# IR_array.net
KiCad netlist of a schematic drawn in Altium Designer
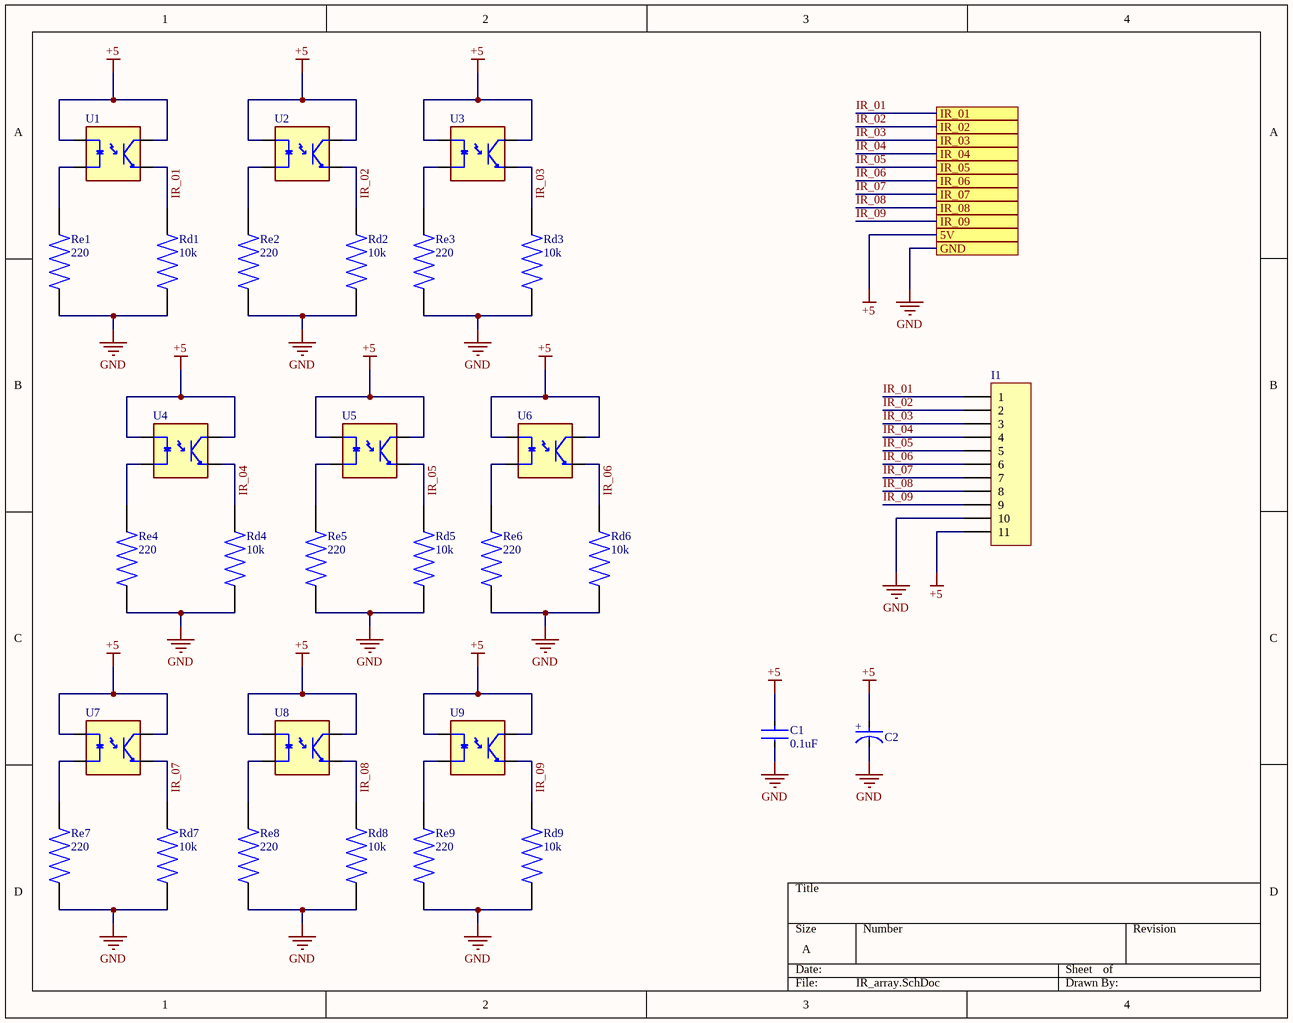
[diagram p0: IR_array.SchDoc]

(export (version "E")
  (design (tool "Eeschema 10.0.6"))
  (components
    (comp (ref "C1")
      (value "0.1uF")
      (footprint "FP-RDE0P1-MFG")
      (description "Ceramic Capacitor 100nF ±10% 25V X7R Radial")
      (fields (field (name "TOLERANCE") "10%"))
      (libsource (lib "0.1uF 25V cap cer TH") (part "CMP-06035-046728-1"))
    )
    (comp (ref "C2")
      (value "ECEA1CKA101I")
      (footprint "FP-RAD-TH-D_6_3_0_5-L_7_1-MFG")
      (description "Aluminum Electrolytic Capacitors (Radial Lead Type) 100uF ±20% 16V")
      (fields (field (name "VOLTAGE") "16V") (field (name "TOLERANCE") "20%"))
      (libsource (lib "100uF 16V cap TH") (part "CMP-05427-001316-1"))
    )
    (comp (ref "I1")
      (value "MHP1x11")
      (footprint "MHPC1x11:MHPC1x11")
      (libsource (lib "MHPC1x11") (part "MHP1x11"))
    )
    (comp (ref "Rd1")
      (value "10k")
      (footprint "RESAD1100W55L680D260")
      (description "1.07 kOhms Â±1% 0.25W, 1/4W Through Hole Resistor Axial - Metal Film")
      (fields (field (name "MF") "Yageo") (field (name "MP") "MFR-25FBF52-1K"))
      (libsource (lib "REG_th") (part "MFR-25FBF52-1K"))
    )
    (comp (ref "Rd2")
      (value "10k")
      (footprint "RESAD1100W55L680D260")
      (description "1.07 kOhms Â±1% 0.25W, 1/4W Through Hole Resistor Axial - Metal Film")
      (fields (field (name "MF") "Yageo") (field (name "MP") "MFR-25FBF52-1K"))
      (libsource (lib "REG_th") (part "MFR-25FBF52-1K"))
    )
    (comp (ref "Rd3")
      (value "10k")
      (footprint "RESAD1100W55L680D260")
      (description "1.07 kOhms Â±1% 0.25W, 1/4W Through Hole Resistor Axial - Metal Film")
      (fields (field (name "MF") "Yageo") (field (name "MP") "MFR-25FBF52-1K"))
      (libsource (lib "REG_th") (part "MFR-25FBF52-1K"))
    )
    (comp (ref "Rd4")
      (value "10k")
      (footprint "RESAD1100W55L680D260")
      (description "1.07 kOhms Â±1% 0.25W, 1/4W Through Hole Resistor Axial - Metal Film")
      (fields (field (name "MF") "Yageo") (field (name "MP") "MFR-25FBF52-1K"))
      (libsource (lib "REG_th") (part "MFR-25FBF52-1K"))
    )
    (comp (ref "Rd5")
      (value "10k")
      (footprint "RESAD1100W55L680D260")
      (description "1.07 kOhms Â±1% 0.25W, 1/4W Through Hole Resistor Axial - Metal Film")
      (fields (field (name "MF") "Yageo") (field (name "MP") "MFR-25FBF52-1K"))
      (libsource (lib "REG_th") (part "MFR-25FBF52-1K"))
    )
    (comp (ref "Rd6")
      (value "10k")
      (footprint "RESAD1100W55L680D260")
      (description "1.07 kOhms Â±1% 0.25W, 1/4W Through Hole Resistor Axial - Metal Film")
      (fields (field (name "MF") "Yageo") (field (name "MP") "MFR-25FBF52-1K"))
      (libsource (lib "REG_th") (part "MFR-25FBF52-1K"))
    )
    (comp (ref "Rd7")
      (value "10k")
      (footprint "RESAD1100W55L680D260")
      (description "1.07 kOhms Â±1% 0.25W, 1/4W Through Hole Resistor Axial - Metal Film")
      (fields (field (name "MF") "Yageo") (field (name "MP") "MFR-25FBF52-1K"))
      (libsource (lib "REG_th") (part "MFR-25FBF52-1K"))
    )
    (comp (ref "Rd8")
      (value "10k")
      (footprint "RESAD1100W55L680D260")
      (description "1.07 kOhms Â±1% 0.25W, 1/4W Through Hole Resistor Axial - Metal Film")
      (fields (field (name "MF") "Yageo") (field (name "MP") "MFR-25FBF52-1K"))
      (libsource (lib "REG_th") (part "MFR-25FBF52-1K"))
    )
    (comp (ref "Rd9")
      (value "10k")
      (footprint "RESAD1100W55L680D260")
      (description "1.07 kOhms Â±1% 0.25W, 1/4W Through Hole Resistor Axial - Metal Film")
      (fields (field (name "MF") "Yageo") (field (name "MP") "MFR-25FBF52-1K"))
      (libsource (lib "REG_th") (part "MFR-25FBF52-1K"))
    )
    (comp (ref "Re1")
      (value "220")
      (footprint "RESAD1100W55L680D260")
      (description "1.07 kOhms Â±1% 0.25W, 1/4W Through Hole Resistor Axial - Metal Film")
      (fields (field (name "MF") "Yageo") (field (name "MP") "MFR-25FBF52-1K"))
      (libsource (lib "REG_th") (part "MFR-25FBF52-1K"))
    )
    (comp (ref "Re2")
      (value "220")
      (footprint "RESAD1100W55L680D260")
      (description "1.07 kOhms Â±1% 0.25W, 1/4W Through Hole Resistor Axial - Metal Film")
      (fields (field (name "MF") "Yageo") (field (name "MP") "MFR-25FBF52-1K"))
      (libsource (lib "REG_th") (part "MFR-25FBF52-1K"))
    )
    (comp (ref "Re3")
      (value "220")
      (footprint "RESAD1100W55L680D260")
      (description "1.07 kOhms Â±1% 0.25W, 1/4W Through Hole Resistor Axial - Metal Film")
      (fields (field (name "MF") "Yageo") (field (name "MP") "MFR-25FBF52-1K"))
      (libsource (lib "REG_th") (part "MFR-25FBF52-1K"))
    )
    (comp (ref "Re4")
      (value "220")
      (footprint "RESAD1100W55L680D260")
      (description "1.07 kOhms Â±1% 0.25W, 1/4W Through Hole Resistor Axial - Metal Film")
      (fields (field (name "MF") "Yageo") (field (name "MP") "MFR-25FBF52-1K"))
      (libsource (lib "REG_th") (part "MFR-25FBF52-1K"))
    )
    (comp (ref "Re5")
      (value "220")
      (footprint "RESAD1100W55L680D260")
      (description "1.07 kOhms Â±1% 0.25W, 1/4W Through Hole Resistor Axial - Metal Film")
      (fields (field (name "MF") "Yageo") (field (name "MP") "MFR-25FBF52-1K"))
      (libsource (lib "REG_th") (part "MFR-25FBF52-1K"))
    )
    (comp (ref "Re6")
      (value "220")
      (footprint "RESAD1100W55L680D260")
      (description "1.07 kOhms Â±1% 0.25W, 1/4W Through Hole Resistor Axial - Metal Film")
      (fields (field (name "MF") "Yageo") (field (name "MP") "MFR-25FBF52-1K"))
      (libsource (lib "REG_th") (part "MFR-25FBF52-1K"))
    )
    (comp (ref "Re7")
      (value "220")
      (footprint "RESAD1100W55L680D260")
      (description "1.07 kOhms Â±1% 0.25W, 1/4W Through Hole Resistor Axial - Metal Film")
      (fields (field (name "MF") "Yageo") (field (name "MP") "MFR-25FBF52-1K"))
      (libsource (lib "REG_th") (part "MFR-25FBF52-1K"))
    )
    (comp (ref "Re8")
      (value "220")
      (footprint "RESAD1100W55L680D260")
      (description "1.07 kOhms Â±1% 0.25W, 1/4W Through Hole Resistor Axial - Metal Film")
      (fields (field (name "MF") "Yageo") (field (name "MP") "MFR-25FBF52-1K"))
      (libsource (lib "REG_th") (part "MFR-25FBF52-1K"))
    )
    (comp (ref "Re9")
      (value "220")
      (footprint "RESAD1100W55L680D260")
      (description "1.07 kOhms Â±1% 0.25W, 1/4W Through Hole Resistor Axial - Metal Film")
      (fields (field (name "MF") "Yageo") (field (name "MP") "MFR-25FBF52-1K"))
      (libsource (lib "REG_th") (part "MFR-25FBF52-1K"))
    )
    (comp (ref "U1")
      (value "TCRT5000")
      (footprint "OPTO_TCRT5000:TCRT5000")
      (description "950 nm 60 mA Through Hole Reflective Optical Sensor with Transistor Output")
      (libsource (lib "TCRT5000") (part "TCRT5000"))
    )
    (comp (ref "U2")
      (value "TCRT5000")
      (footprint "OPTO_TCRT5000:TCRT5000")
      (description "950 nm 60 mA Through Hole Reflective Optical Sensor with Transistor Output")
      (libsource (lib "TCRT5000") (part "TCRT5000"))
    )
    (comp (ref "U3")
      (value "TCRT5000")
      (footprint "OPTO_TCRT5000:TCRT5000")
      (description "950 nm 60 mA Through Hole Reflective Optical Sensor with Transistor Output")
      (libsource (lib "TCRT5000") (part "TCRT5000"))
    )
    (comp (ref "U4")
      (value "TCRT5000")
      (footprint "OPTO_TCRT5000:TCRT5000")
      (description "950 nm 60 mA Through Hole Reflective Optical Sensor with Transistor Output")
      (libsource (lib "TCRT5000") (part "TCRT5000"))
    )
    (comp (ref "U5")
      (value "TCRT5000")
      (footprint "OPTO_TCRT5000:TCRT5000")
      (description "950 nm 60 mA Through Hole Reflective Optical Sensor with Transistor Output")
      (libsource (lib "TCRT5000") (part "TCRT5000"))
    )
    (comp (ref "U6")
      (value "TCRT5000")
      (footprint "OPTO_TCRT5000:TCRT5000")
      (description "950 nm 60 mA Through Hole Reflective Optical Sensor with Transistor Output")
      (libsource (lib "TCRT5000") (part "TCRT5000"))
    )
    (comp (ref "U7")
      (value "TCRT5000")
      (footprint "OPTO_TCRT5000:TCRT5000")
      (description "950 nm 60 mA Through Hole Reflective Optical Sensor with Transistor Output")
      (libsource (lib "TCRT5000") (part "TCRT5000"))
    )
    (comp (ref "U8")
      (value "TCRT5000")
      (footprint "OPTO_TCRT5000:TCRT5000")
      (description "950 nm 60 mA Through Hole Reflective Optical Sensor with Transistor Output")
      (libsource (lib "TCRT5000") (part "TCRT5000"))
    )
    (comp (ref "U9")
      (value "TCRT5000")
      (footprint "OPTO_TCRT5000:TCRT5000")
      (description "950 nm 60 mA Through Hole Reflective Optical Sensor with Transistor Output")
      (libsource (lib "TCRT5000") (part "TCRT5000"))
    )
  )
  (nets
    (net (code "1") (name "+5") (class "Default")
      (node (ref "C1") (pin "1") (pinfunction "1_1") (pintype "passive"))
      (node (ref "C2") (pin "2") (pinfunction "A_2") (pintype "passive"))
      (node (ref "I1") (pin "11") (pinfunction "11_11") (pintype "passive"))
      (node (ref "U1") (pin "A") (pinfunction "A_A") (pintype "passive"))
      (node (ref "U1") (pin "COLL") (pinfunction "COLL_COLL") (pintype "passive"))
      (node (ref "U2") (pin "A") (pinfunction "A_A") (pintype "passive"))
      (node (ref "U2") (pin "COLL") (pinfunction "COLL_COLL") (pintype "passive"))
      (node (ref "U3") (pin "A") (pinfunction "A_A") (pintype "passive"))
      (node (ref "U3") (pin "COLL") (pinfunction "COLL_COLL") (pintype "passive"))
      (node (ref "U4") (pin "A") (pinfunction "A_A") (pintype "passive"))
      (node (ref "U4") (pin "COLL") (pinfunction "COLL_COLL") (pintype "passive"))
      (node (ref "U5") (pin "A") (pinfunction "A_A") (pintype "passive"))
      (node (ref "U5") (pin "COLL") (pinfunction "COLL_COLL") (pintype "passive"))
      (node (ref "U6") (pin "A") (pinfunction "A_A") (pintype "passive"))
      (node (ref "U6") (pin "COLL") (pinfunction "COLL_COLL") (pintype "passive"))
      (node (ref "U7") (pin "A") (pinfunction "A_A") (pintype "passive"))
      (node (ref "U7") (pin "COLL") (pinfunction "COLL_COLL") (pintype "passive"))
      (node (ref "U8") (pin "A") (pinfunction "A_A") (pintype "passive"))
      (node (ref "U8") (pin "COLL") (pinfunction "COLL_COLL") (pintype "passive"))
      (node (ref "U9") (pin "A") (pinfunction "A_A") (pintype "passive"))
      (node (ref "U9") (pin "COLL") (pinfunction "COLL_COLL") (pintype "passive"))
    )
    (net (code "2") (name "/IR_01") (class "Default")
      (node (ref "I1") (pin "1") (pinfunction "1_1") (pintype "passive"))
      (node (ref "Rd1") (pin "2") (pinfunction "2_2") (pintype "passive"))
      (node (ref "U1") (pin "E") (pinfunction "E_E") (pintype "passive"))
    )
    (net (code "3") (name "/IR_02") (class "Default")
      (node (ref "I1") (pin "2") (pinfunction "2_2") (pintype "passive"))
      (node (ref "Rd2") (pin "2") (pinfunction "2_2") (pintype "passive"))
      (node (ref "U2") (pin "E") (pinfunction "E_E") (pintype "passive"))
    )
    (net (code "4") (name "/IR_03") (class "Default")
      (node (ref "I1") (pin "3") (pinfunction "3_3") (pintype "passive"))
      (node (ref "Rd3") (pin "2") (pinfunction "2_2") (pintype "passive"))
      (node (ref "U3") (pin "E") (pinfunction "E_E") (pintype "passive"))
    )
    (net (code "5") (name "/IR_04") (class "Default")
      (node (ref "I1") (pin "4") (pinfunction "4_4") (pintype "passive"))
      (node (ref "Rd4") (pin "2") (pinfunction "2_2") (pintype "passive"))
      (node (ref "U4") (pin "E") (pinfunction "E_E") (pintype "passive"))
    )
    (net (code "6") (name "/IR_05") (class "Default")
      (node (ref "I1") (pin "5") (pinfunction "5_5") (pintype "passive"))
      (node (ref "Rd5") (pin "2") (pinfunction "2_2") (pintype "passive"))
      (node (ref "U5") (pin "E") (pinfunction "E_E") (pintype "passive"))
    )
    (net (code "7") (name "/IR_06") (class "Default")
      (node (ref "I1") (pin "6") (pinfunction "6_6") (pintype "passive"))
      (node (ref "Rd6") (pin "2") (pinfunction "2_2") (pintype "passive"))
      (node (ref "U6") (pin "E") (pinfunction "E_E") (pintype "passive"))
    )
    (net (code "8") (name "/IR_07") (class "Default")
      (node (ref "I1") (pin "7") (pinfunction "7_7") (pintype "passive"))
      (node (ref "Rd7") (pin "2") (pinfunction "2_2") (pintype "passive"))
      (node (ref "U7") (pin "E") (pinfunction "E_E") (pintype "passive"))
    )
    (net (code "9") (name "/IR_08") (class "Default")
      (node (ref "I1") (pin "8") (pinfunction "8_8") (pintype "passive"))
      (node (ref "Rd8") (pin "2") (pinfunction "2_2") (pintype "passive"))
      (node (ref "U8") (pin "E") (pinfunction "E_E") (pintype "passive"))
    )
    (net (code "10") (name "/IR_09") (class "Default")
      (node (ref "I1") (pin "9") (pinfunction "9_9") (pintype "passive"))
      (node (ref "Rd9") (pin "2") (pinfunction "2_2") (pintype "passive"))
      (node (ref "U9") (pin "E") (pinfunction "E_E") (pintype "passive"))
    )
    (net (code "11") (name "GND") (class "Default")
      (node (ref "C1") (pin "2") (pinfunction "2_2") (pintype "passive"))
      (node (ref "C2") (pin "1") (pinfunction "C_1") (pintype "passive"))
      (node (ref "I1") (pin "10") (pinfunction "10_10") (pintype "passive"))
      (node (ref "Rd1") (pin "1") (pinfunction "1_1") (pintype "passive"))
      (node (ref "Rd2") (pin "1") (pinfunction "1_1") (pintype "passive"))
      (node (ref "Rd3") (pin "1") (pinfunction "1_1") (pintype "passive"))
      (node (ref "Rd4") (pin "1") (pinfunction "1_1") (pintype "passive"))
      (node (ref "Rd5") (pin "1") (pinfunction "1_1") (pintype "passive"))
      (node (ref "Rd6") (pin "1") (pinfunction "1_1") (pintype "passive"))
      (node (ref "Rd7") (pin "1") (pinfunction "1_1") (pintype "passive"))
      (node (ref "Rd8") (pin "1") (pinfunction "1_1") (pintype "passive"))
      (node (ref "Rd9") (pin "1") (pinfunction "1_1") (pintype "passive"))
      (node (ref "Re1") (pin "1") (pinfunction "1_1") (pintype "passive"))
      (node (ref "Re2") (pin "1") (pinfunction "1_1") (pintype "passive"))
      (node (ref "Re3") (pin "1") (pinfunction "1_1") (pintype "passive"))
      (node (ref "Re4") (pin "1") (pinfunction "1_1") (pintype "passive"))
      (node (ref "Re5") (pin "1") (pinfunction "1_1") (pintype "passive"))
      (node (ref "Re6") (pin "1") (pinfunction "1_1") (pintype "passive"))
      (node (ref "Re7") (pin "1") (pinfunction "1_1") (pintype "passive"))
      (node (ref "Re8") (pin "1") (pinfunction "1_1") (pintype "passive"))
      (node (ref "Re9") (pin "1") (pinfunction "1_1") (pintype "passive"))
    )
    (net (code "12") (name "Net-(Re1-Pad2)") (class "Default")
      (node (ref "Re1") (pin "2") (pinfunction "2_2") (pintype "passive"))
      (node (ref "U1") (pin "CATH") (pinfunction "CATH_CATH") (pintype "passive"))
    )
    (net (code "13") (name "Net-(Re2-Pad2)") (class "Default")
      (node (ref "Re2") (pin "2") (pinfunction "2_2") (pintype "passive"))
      (node (ref "U2") (pin "CATH") (pinfunction "CATH_CATH") (pintype "passive"))
    )
    (net (code "14") (name "Net-(Re3-Pad2)") (class "Default")
      (node (ref "Re3") (pin "2") (pinfunction "2_2") (pintype "passive"))
      (node (ref "U3") (pin "CATH") (pinfunction "CATH_CATH") (pintype "passive"))
    )
    (net (code "15") (name "Net-(Re4-Pad2)") (class "Default")
      (node (ref "Re4") (pin "2") (pinfunction "2_2") (pintype "passive"))
      (node (ref "U4") (pin "CATH") (pinfunction "CATH_CATH") (pintype "passive"))
    )
    (net (code "16") (name "Net-(Re5-Pad2)") (class "Default")
      (node (ref "Re5") (pin "2") (pinfunction "2_2") (pintype "passive"))
      (node (ref "U5") (pin "CATH") (pinfunction "CATH_CATH") (pintype "passive"))
    )
    (net (code "17") (name "Net-(Re6-Pad2)") (class "Default")
      (node (ref "Re6") (pin "2") (pinfunction "2_2") (pintype "passive"))
      (node (ref "U6") (pin "CATH") (pinfunction "CATH_CATH") (pintype "passive"))
    )
    (net (code "18") (name "Net-(Re7-Pad2)") (class "Default")
      (node (ref "Re7") (pin "2") (pinfunction "2_2") (pintype "passive"))
      (node (ref "U7") (pin "CATH") (pinfunction "CATH_CATH") (pintype "passive"))
    )
    (net (code "19") (name "Net-(Re8-Pad2)") (class "Default")
      (node (ref "Re8") (pin "2") (pinfunction "2_2") (pintype "passive"))
      (node (ref "U8") (pin "CATH") (pinfunction "CATH_CATH") (pintype "passive"))
    )
    (net (code "20") (name "Net-(Re9-Pad2)") (class "Default")
      (node (ref "Re9") (pin "2") (pinfunction "2_2") (pintype "passive"))
      (node (ref "U9") (pin "CATH") (pinfunction "CATH_CATH") (pintype "passive"))
    )
  )
)
